# Temp_and_Humidity_Sensor.net
KiCad netlist of a schematic drawn in Altium Designer
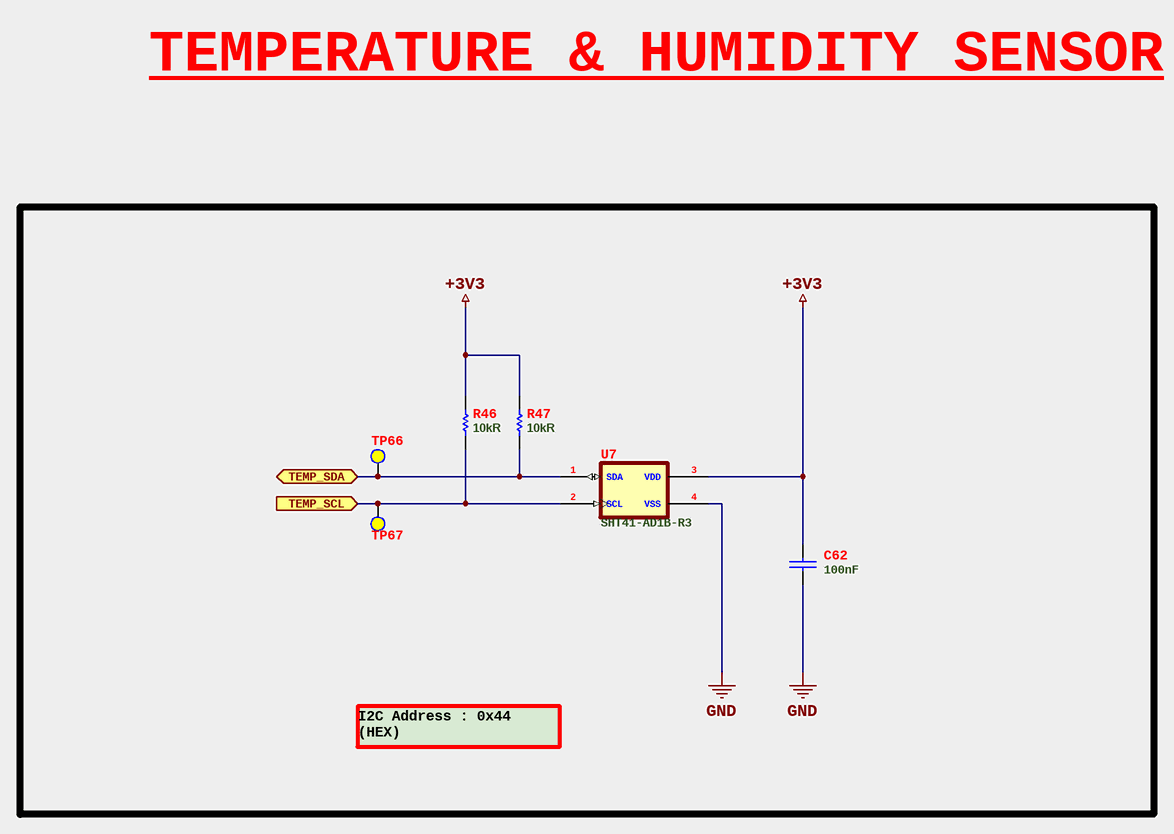
[diagram p0: Temp and Humidity Sensor.SchDoc]

(export (version "E")
  (design (tool "Eeschema 10.0.6"))
  (components
    (comp (ref "C62")
      (value "100nF")
      (footprint "CAP_0603")
      (description "0.1 µF ±10% 50V Ceramic Capacitor X7R 0603 (1608 Metric)")
      (fields
        (field (name "MANUFACTURER") "Yageo")
        (field (name "MANUFACTURER PART NUMBER") "CC0603KRX7R9BB104")
      )
      (libsource (lib "Cellar Watchdog") (part "CAP_0.1uF-50V-10%_0603"))
    )
    (comp (ref "R46")
      (value "10kR")
      (footprint "RES_0603")
      (description "10 kOhms ±1% 0.1W, 1/10W Chip Resistor 0603 (1608 Metric) Moisture Resistant Thick Film")
      (fields
        (field (name "MANUFACTURER") "Yageo")
        (field (name "MANUFACTURER PART NUMBER") "RC0603FR-0710KL")
      )
      (libsource (lib "Cellar Watchdog") (part "RES_10kR-100mW-1%_0603"))
    )
    (comp (ref "R47")
      (value "10kR")
      (footprint "RES_0603")
      (description "10 kOhms ±1% 0.1W, 1/10W Chip Resistor 0603 (1608 Metric) Moisture Resistant Thick Film")
      (fields
        (field (name "MANUFACTURER") "Yageo")
        (field (name "MANUFACTURER PART NUMBER") "RC0603FR-0710KL")
      )
      (libsource (lib "Cellar Watchdog") (part "RES_10kR-100mW-1%_0603"))
    )
    (comp (ref "TP66")
      (value "TEMP_SDA")
      (footprint "TEST POINT HOLE")
      (description "PCB Test Point")
      (libsource (lib "Cellar Watchdog") (part "Test Point"))
    )
    (comp (ref "TP67")
      (value "TEMP_SCL")
      (footprint "TEST POINT HOLE")
      (description "PCB Test Point")
      (libsource (lib "Cellar Watchdog") (part "Test Point"))
    )
    (comp (ref "U7")
      (value "SHT41-AD1B-R3")
      (footprint "IC_SENSIRION_SHT41-AD1B-R3")
      (description "Humidity, Temperature 0 ~ 100% RH I²C ±1.8% RH 4 s Surface Mount")
      (fields (field (name "MANUFACTURER") "Sensirion"))
      (libsource (lib "Cellar Watchdog") (part "IC_SHT41-AD1B-R3"))
    )
  )
  (nets
    (net (code "1") (name "+3V3") (class "Default")
      (node (ref "C62") (pin "1") (pinfunction "1_1") (pintype "passive"))
      (node (ref "R46") (pin "2") (pinfunction "2_2") (pintype "passive"))
      (node (ref "R47") (pin "2") (pinfunction "2_2") (pintype "passive"))
      (node (ref "U7") (pin "3") (pinfunction "VDD_3") (pintype "power_in"))
    )
    (net (code "2") (name "/TEMP_SCL") (class "Default")
      (node (ref "R46") (pin "1") (pinfunction "1_1") (pintype "passive"))
      (node (ref "TP67") (pin "TP") (pinfunction "TP_TP") (pintype "passive"))
      (node (ref "U7") (pin "2") (pinfunction "SCL_2") (pintype "input"))
    )
    (net (code "3") (name "/TEMP_SDA") (class "Default")
      (node (ref "R47") (pin "1") (pinfunction "1_1") (pintype "passive"))
      (node (ref "TP66") (pin "TP") (pinfunction "TP_TP") (pintype "passive"))
      (node (ref "U7") (pin "1") (pinfunction "SDA_1") (pintype "bidirectional"))
    )
    (net (code "4") (name "GND") (class "Default")
      (node (ref "C62") (pin "2") (pinfunction "2_2") (pintype "passive"))
      (node (ref "U7") (pin "4") (pinfunction "VSS_4") (pintype "power_in"))
    )
  )
)
